# termoresistenza_v1_rev1.net
KiCad netlist of a schematic drawn in EAGLE
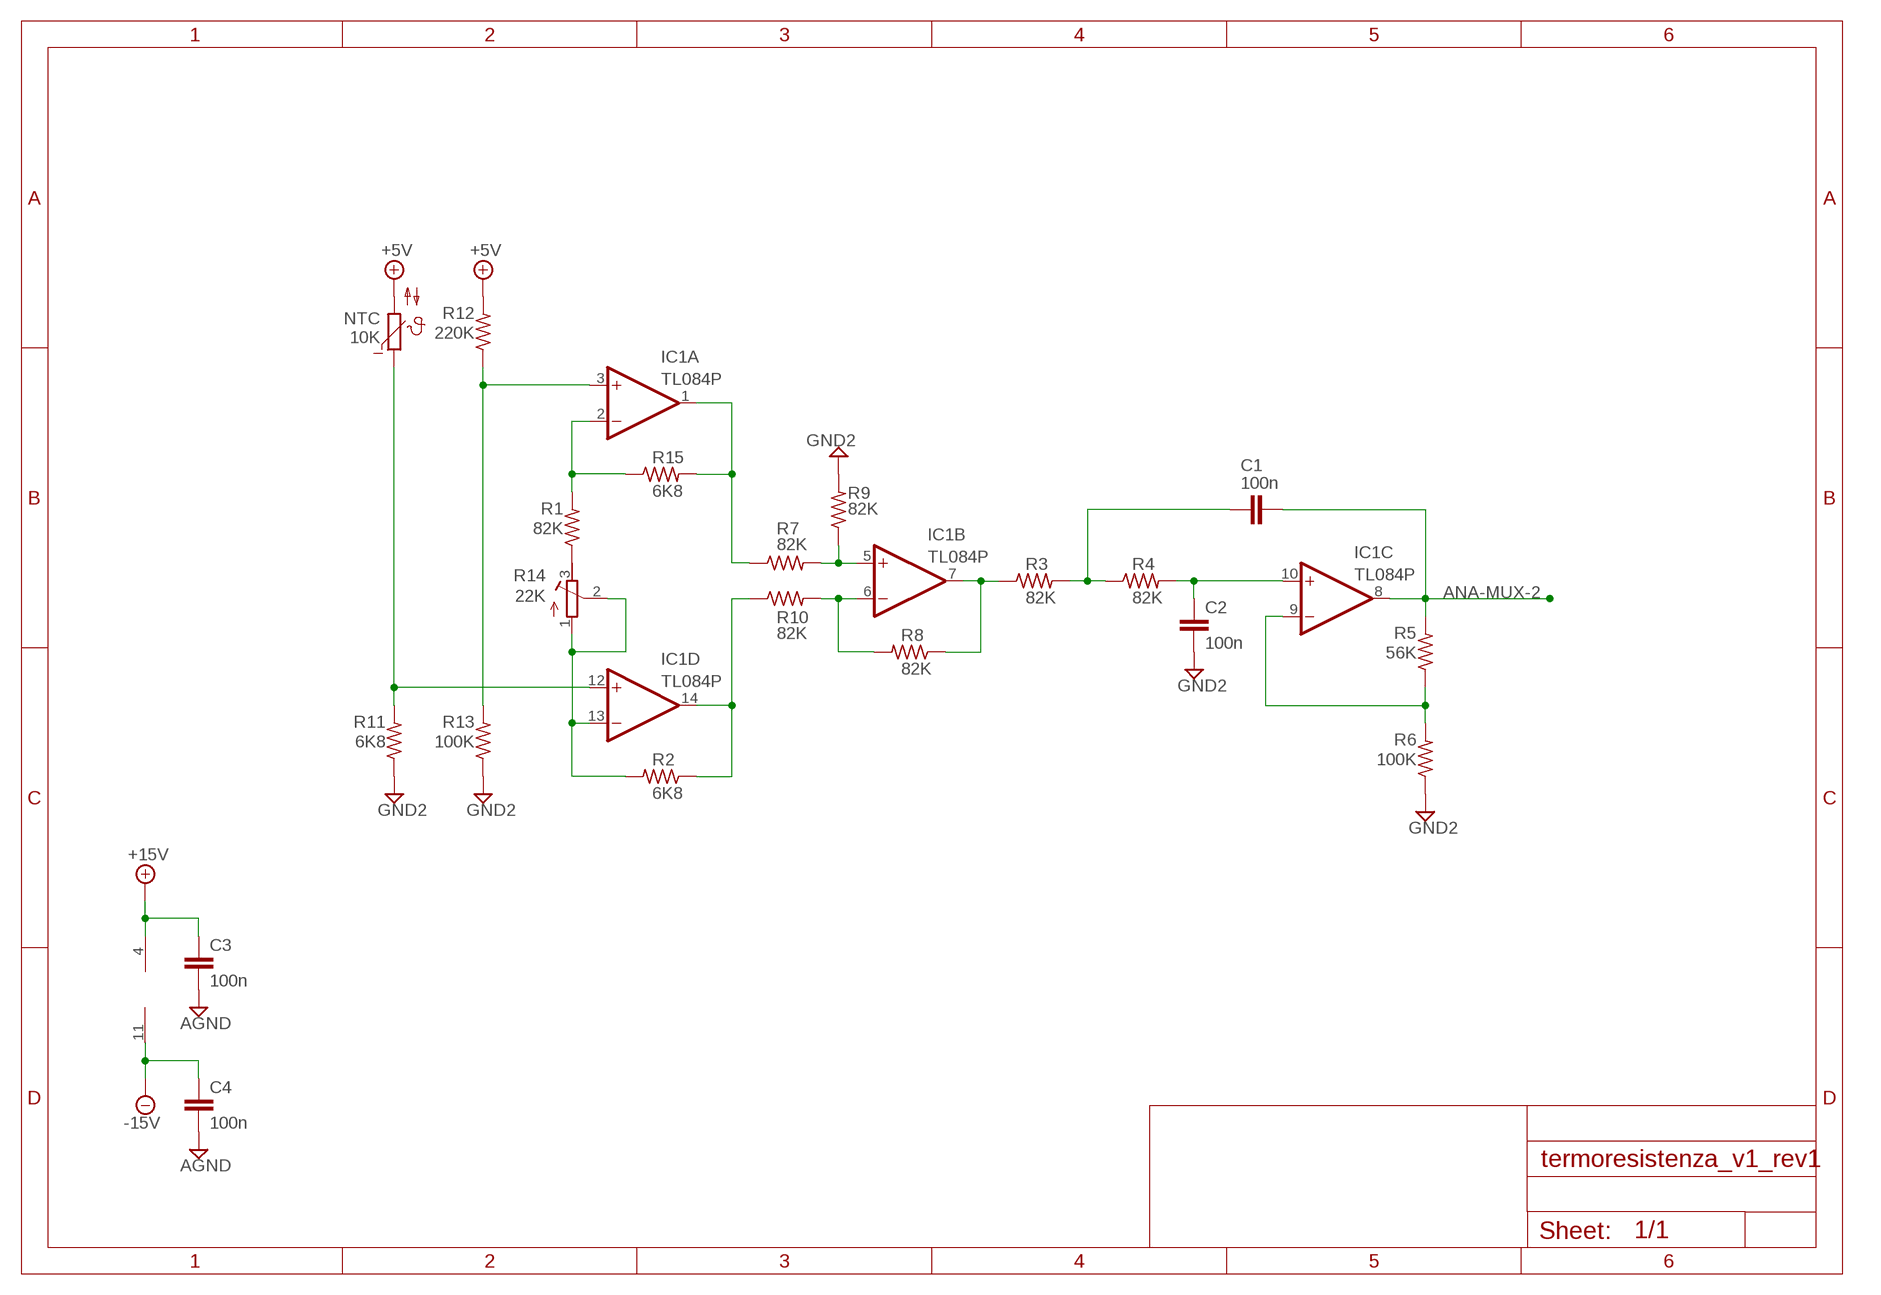
[diagram p0: schematic, sheet 1]

(export (version "E")
  (design (tool "Eeschema 10.0.6"))
  (components
    (comp (ref "C1")
      (value "100n")
      (footprint "eagle-import:C025-025X050")
      (libsource (lib "eagle-import") (part "C-EU025-025X050"))
    )
    (comp (ref "C2")
      (value "100n")
      (footprint "eagle-import:C025-025X050")
      (libsource (lib "eagle-import") (part "C-EU025-025X050"))
    )
    (comp (ref "C3")
      (value "100n")
      (footprint "eagle-import:C025-025X050")
      (libsource (lib "eagle-import") (part "C-EU025-025X050"))
    )
    (comp (ref "C4")
      (value "100n")
      (footprint "eagle-import:C025-025X050")
      (libsource (lib "eagle-import") (part "C-EU025-025X050"))
    )
    (comp (ref "IC1")
      (value "TL084P")
      (footprint "eagle-import:DIL14")
      (libsource (lib "eagle-import") (part "TL084P"))
    )
    (comp (ref "NTC")
      (value "10K")
      (footprint "eagle-import:P640")
      (libsource (lib "eagle-import") (part "NTC640"))
    )
    (comp (ref "R1")
      (value "82K")
      (footprint "eagle-import:0204_7")
      (libsource (lib "eagle-import") (part "R-US_0204/7"))
    )
    (comp (ref "R2")
      (value "6K8")
      (footprint "eagle-import:0204_7")
      (libsource (lib "eagle-import") (part "R-US_0204/7"))
    )
    (comp (ref "R3")
      (value "82K")
      (footprint "eagle-import:0204_7")
      (libsource (lib "eagle-import") (part "R-US_0204/7"))
    )
    (comp (ref "R4")
      (value "82K")
      (footprint "eagle-import:0204_7")
      (libsource (lib "eagle-import") (part "R-US_0204/7"))
    )
    (comp (ref "R5")
      (value "56K")
      (footprint "eagle-import:0204_7")
      (libsource (lib "eagle-import") (part "R-US_0204/7"))
    )
    (comp (ref "R6")
      (value "100K")
      (footprint "eagle-import:0204_7")
      (libsource (lib "eagle-import") (part "R-US_0204/7"))
    )
    (comp (ref "R7")
      (value "82K")
      (footprint "eagle-import:0204_7")
      (libsource (lib "eagle-import") (part "R-US_0204/7"))
    )
    (comp (ref "R8")
      (value "82K")
      (footprint "eagle-import:0204_7")
      (libsource (lib "eagle-import") (part "R-US_0204/7"))
    )
    (comp (ref "R9")
      (value "82K")
      (footprint "eagle-import:0204_7")
      (libsource (lib "eagle-import") (part "R-US_0204/7"))
    )
    (comp (ref "R10")
      (value "82K")
      (footprint "eagle-import:0204_7")
      (libsource (lib "eagle-import") (part "R-US_0204/7"))
    )
    (comp (ref "R11")
      (value "6K8")
      (footprint "eagle-import:0204_7")
      (libsource (lib "eagle-import") (part "R-US_0204/7"))
    )
    (comp (ref "R12")
      (value "220K")
      (footprint "eagle-import:0204_7")
      (libsource (lib "eagle-import") (part "R-US_0204/7"))
    )
    (comp (ref "R13")
      (value "100K")
      (footprint "eagle-import:0204_7")
      (libsource (lib "eagle-import") (part "R-US_0204/7"))
    )
    (comp (ref "R14")
      (value "22K")
      (footprint "eagle-import:RTRIM64W")
      (libsource (lib "eagle-import") (part "R-TRIMM64W"))
    )
    (comp (ref "R15")
      (value "6K8")
      (footprint "eagle-import:0204_7")
      (libsource (lib "eagle-import") (part "R-US_0204/7"))
    )
  )
  (nets
    (net (code "1") (name "+5V") (class "Default")
      (node (ref "NTC") (pin "2") (pinfunction "2_2") (pintype "passive"))
      (node (ref "R12") (pin "2") (pinfunction "2_2") (pintype "passive"))
    )
    (net (code "2") (name "+15V") (class "Default")
      (node (ref "C3") (pin "1") (pinfunction "1_1") (pintype "passive"))
      (node (ref "IC1") (pin "4") (pinfunction "V+_4") (pintype "power_in"))
    )
    (net (code "3") (name "-15V") (class "Default")
      (node (ref "C4") (pin "1") (pinfunction "1_1") (pintype "passive"))
      (node (ref "IC1") (pin "11") (pinfunction "V-_11") (pintype "power_in"))
    )
    (net (code "4") (name "/ANA-MUX-2") (class "Default")
      (node (ref "C1") (pin "2") (pinfunction "2_2") (pintype "passive"))
      (node (ref "IC1") (pin "8") (pinfunction "OUT_8") (pintype "output"))
      (node (ref "R5") (pin "2") (pinfunction "2_2") (pintype "passive"))
    )
    (net (code "5") (name "AGND") (class "Default")
      (node (ref "C3") (pin "2") (pinfunction "2_2") (pintype "passive"))
      (node (ref "C4") (pin "2") (pinfunction "2_2") (pintype "passive"))
    )
    (net (code "6") (name "GND2") (class "Default")
      (node (ref "C2") (pin "2") (pinfunction "2_2") (pintype "passive"))
      (node (ref "R11") (pin "1") (pinfunction "1_1") (pintype "passive"))
      (node (ref "R13") (pin "1") (pinfunction "1_1") (pintype "passive"))
      (node (ref "R6") (pin "1") (pinfunction "1_1") (pintype "passive"))
      (node (ref "R9") (pin "2") (pinfunction "2_2") (pintype "passive"))
    )
    (net (code "7") (name "Net-(C1-Pad1)") (class "Default")
      (node (ref "C1") (pin "1") (pinfunction "1_1") (pintype "passive"))
      (node (ref "R3") (pin "2") (pinfunction "2_2") (pintype "passive"))
      (node (ref "R4") (pin "1") (pinfunction "1_1") (pintype "passive"))
    )
    (net (code "8") (name "Net-(IC1A-+IN)") (class "Default")
      (node (ref "IC1") (pin "3") (pinfunction "+IN_3") (pintype "input"))
      (node (ref "R12") (pin "1") (pinfunction "1_1") (pintype "passive"))
      (node (ref "R13") (pin "2") (pinfunction "2_2") (pintype "passive"))
    )
    (net (code "9") (name "Net-(IC1A--IN)") (class "Default")
      (node (ref "IC1") (pin "2") (pinfunction "-IN_2") (pintype "input"))
      (node (ref "R1") (pin "2") (pinfunction "2_2") (pintype "passive"))
      (node (ref "R15") (pin "1") (pinfunction "1_1") (pintype "passive"))
    )
    (net (code "10") (name "Net-(IC1A-OUT)") (class "Default")
      (node (ref "IC1") (pin "1") (pinfunction "OUT_1") (pintype "output"))
      (node (ref "R10") (pin "1") (pinfunction "1_1") (pintype "passive"))
      (node (ref "R15") (pin "2") (pinfunction "2_2") (pintype "passive"))
    )
    (net (code "11") (name "Net-(IC1B-+IN)") (class "Default")
      (node (ref "IC1") (pin "5") (pinfunction "+IN_5") (pintype "input"))
      (node (ref "R10") (pin "2") (pinfunction "2_2") (pintype "passive"))
      (node (ref "R9") (pin "1") (pinfunction "1_1") (pintype "passive"))
    )
    (net (code "12") (name "Net-(IC1B--IN)") (class "Default")
      (node (ref "IC1") (pin "6") (pinfunction "-IN_6") (pintype "input"))
      (node (ref "R7") (pin "2") (pinfunction "2_2") (pintype "passive"))
      (node (ref "R8") (pin "2") (pinfunction "2_2") (pintype "passive"))
    )
    (net (code "13") (name "Net-(IC1B-OUT)") (class "Default")
      (node (ref "IC1") (pin "7") (pinfunction "OUT_7") (pintype "output"))
      (node (ref "R3") (pin "1") (pinfunction "1_1") (pintype "passive"))
      (node (ref "R8") (pin "1") (pinfunction "1_1") (pintype "passive"))
    )
    (net (code "14") (name "Net-(IC1C-+IN)") (class "Default")
      (node (ref "C2") (pin "1") (pinfunction "1_1") (pintype "passive"))
      (node (ref "IC1") (pin "10") (pinfunction "+IN_10") (pintype "input"))
      (node (ref "R4") (pin "2") (pinfunction "2_2") (pintype "passive"))
    )
    (net (code "15") (name "Net-(IC1C--IN)") (class "Default")
      (node (ref "IC1") (pin "9") (pinfunction "-IN_9") (pintype "input"))
      (node (ref "R5") (pin "1") (pinfunction "1_1") (pintype "passive"))
      (node (ref "R6") (pin "2") (pinfunction "2_2") (pintype "passive"))
    )
    (net (code "16") (name "Net-(IC1D-+IN)") (class "Default")
      (node (ref "IC1") (pin "12") (pinfunction "+IN_12") (pintype "input"))
      (node (ref "NTC") (pin "1") (pinfunction "1_1") (pintype "passive"))
      (node (ref "R11") (pin "2") (pinfunction "2_2") (pintype "passive"))
    )
    (net (code "17") (name "Net-(IC1D--IN)") (class "Default")
      (node (ref "IC1") (pin "13") (pinfunction "-IN_13") (pintype "input"))
      (node (ref "R14") (pin "1") (pinfunction "E_1") (pintype "passive"))
      (node (ref "R14") (pin "2") (pinfunction "S_2") (pintype "passive"))
      (node (ref "R2") (pin "2") (pinfunction "2_2") (pintype "passive"))
    )
    (net (code "18") (name "Net-(IC1D-OUT)") (class "Default")
      (node (ref "IC1") (pin "14") (pinfunction "OUT_14") (pintype "output"))
      (node (ref "R2") (pin "1") (pinfunction "1_1") (pintype "passive"))
      (node (ref "R7") (pin "1") (pinfunction "1_1") (pintype "passive"))
    )
    (net (code "19") (name "Net-(R14-A)") (class "Default")
      (node (ref "R1") (pin "1") (pinfunction "1_1") (pintype "passive"))
      (node (ref "R14") (pin "3") (pinfunction "A_3") (pintype "passive"))
    )
  )
)
